# nm_mcu.net
KiCad netlist of a schematic drawn in Altium Designer
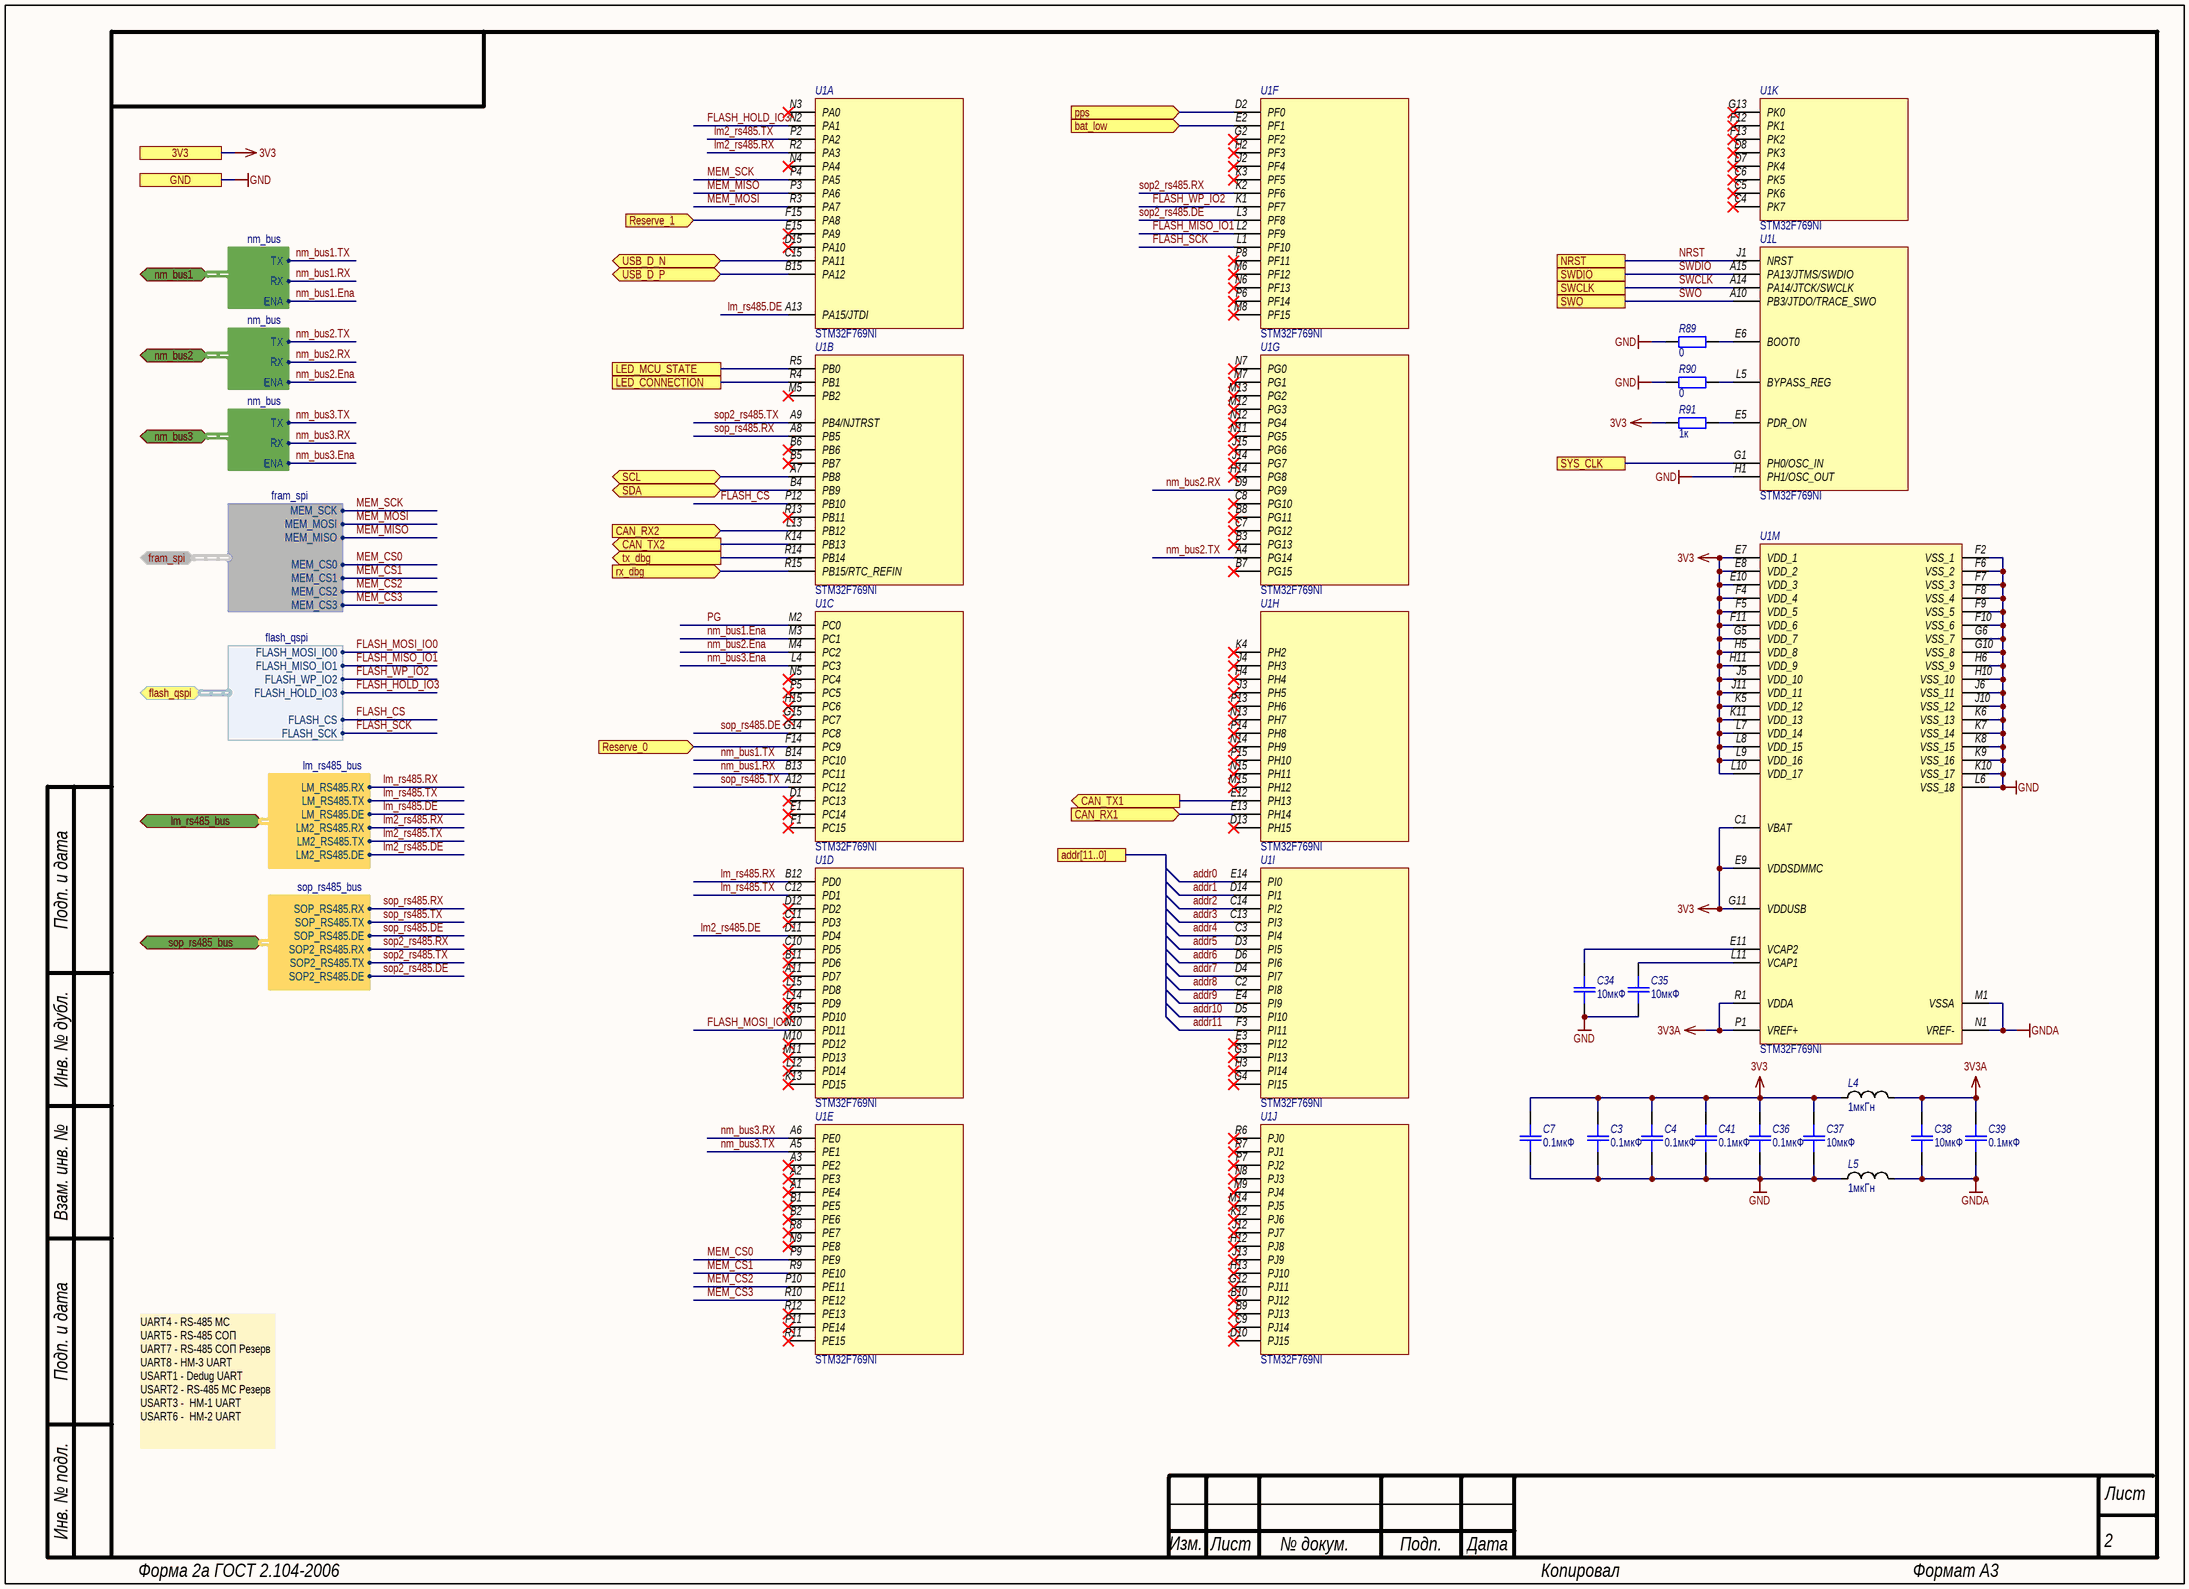
[diagram p0: nm_mcu.SchDoc]

(export (version "E")
  (design (tool "Eeschema 10.0.6"))
  (components
    (comp (ref "C3")
      (value "0.1мкФ")
      (footprint "SMD_C0603")
      (description "Capacitor")
      (libsource (lib "Passive") (part "Capacitor"))
    )
    (comp (ref "C4")
      (value "0.1мкФ")
      (footprint "SMD_C0603")
      (description "Capacitor")
      (libsource (lib "Passive") (part "Capacitor"))
    )
    (comp (ref "C7")
      (value "0.1мкФ")
      (footprint "SMD_C0603")
      (description "Capacitor")
      (libsource (lib "Passive") (part "Capacitor"))
    )
    (comp (ref "C34")
      (value "10мкФ")
      (footprint "SMD_C0603")
      (description "Capacitor")
      (libsource (lib "Passive") (part "Capacitor"))
    )
    (comp (ref "C35")
      (value "10мкФ")
      (footprint "SMD_C0603")
      (description "Capacitor")
      (libsource (lib "Passive") (part "Capacitor"))
    )
    (comp (ref "C36")
      (value "0.1мкФ")
      (footprint "SMD_C0603")
      (description "Capacitor")
      (libsource (lib "Passive") (part "Capacitor"))
    )
    (comp (ref "C37")
      (value "10мкФ")
      (footprint "SMD_C0603")
      (description "Capacitor")
      (libsource (lib "Passive") (part "Capacitor"))
    )
    (comp (ref "C38")
      (value "10мкФ")
      (footprint "SMD_C0603")
      (description "Capacitor")
      (libsource (lib "Passive") (part "Capacitor"))
    )
    (comp (ref "C39")
      (value "0.1мкФ")
      (footprint "SMD_C0603")
      (description "Capacitor")
      (libsource (lib "Passive") (part "Capacitor"))
    )
    (comp (ref "C41")
      (value "0.1мкФ")
      (footprint "SMD_C0603")
      (description "Capacitor")
      (libsource (lib "Passive") (part "Capacitor"))
    )
    (comp (ref "L4")
      (value "1мкГн")
      (footprint "SMD_0805")
      (description "Inductor")
      (libsource (lib "Passive") (part "Inductor"))
    )
    (comp (ref "L5")
      (value "1мкГн")
      (footprint "SMD_0805")
      (description "Inductor")
      (libsource (lib "Passive") (part "Inductor"))
    )
    (comp (ref "R89")
      (value "0")
      (footprint "SMD_0603")
      (description "Resistor")
      (libsource (lib "Passive") (part "Resistor"))
    )
    (comp (ref "R90")
      (value "0")
      (footprint "SMD_0603")
      (description "Resistor")
      (libsource (lib "Passive") (part "Resistor"))
    )
    (comp (ref "R91")
      (value "1к")
      (footprint "SMD_0603")
      (description "Resistor")
      (libsource (lib "Passive") (part "Resistor"))
    )
    (comp (ref "U1")
      (value "STM32F769NI")
      (footprint "BGA216C80P15X15_1300X1300X110")
      (fields (field (name "НАИМЕНОВАНИЕ") "STM32F769NI"))
      (libsource (lib "STM32F769NI") (part "STM32F769NI"))
    )
  )
  (nets
    (net (code "6") (name "/CAN_RX1") (class "Default")
      (node (ref "U1") (pin "E13") (pinfunction "PH14_E13") (pintype "passive"))
    )
    (net (code "7") (name "/CAN_RX2") (class "Default")
      (node (ref "U1") (pin "L13") (pinfunction "PB12_L13") (pintype "passive"))
    )
    (net (code "8") (name "/CAN_TX1") (class "Default")
      (node (ref "U1") (pin "E12") (pinfunction "PH13_E12") (pintype "passive"))
    )
    (net (code "9") (name "/CAN_TX2") (class "Default")
      (node (ref "U1") (pin "K14") (pinfunction "PB13_K14") (pintype "passive"))
    )
    (net (code "10") (name "/FLASH_CS") (class "Default")
      (node (ref "U1") (pin "P12") (pinfunction "PB10_P12") (pintype "passive"))
    )
    (net (code "11") (name "/FLASH_HOLD_IO3") (class "Default")
      (node (ref "U1") (pin "N2") (pinfunction "PA1_N2") (pintype "passive"))
    )
    (net (code "12") (name "/FLASH_MISO_IO1") (class "Default")
      (node (ref "U1") (pin "L2") (pinfunction "PF9_L2") (pintype "passive"))
    )
    (net (code "13") (name "/FLASH_MOSI_IO0") (class "Default")
      (node (ref "U1") (pin "N10") (pinfunction "PD11_N10") (pintype "passive"))
    )
    (net (code "14") (name "/FLASH_SCK") (class "Default")
      (node (ref "U1") (pin "L1") (pinfunction "PF10_L1") (pintype "passive"))
    )
    (net (code "15") (name "/FLASH_WP_IO2") (class "Default")
      (node (ref "U1") (pin "K1") (pinfunction "PF7_K1") (pintype "passive"))
    )
    (net (code "16") (name "/LED_CONNECTION") (class "Default")
      (node (ref "U1") (pin "R4") (pinfunction "PB1_R4") (pintype "passive"))
    )
    (net (code "17") (name "/LED_MCU_STATE") (class "Default")
      (node (ref "U1") (pin "R5") (pinfunction "PB0_R5") (pintype "passive"))
    )
    (net (code "18") (name "/MEM_CS0") (class "Default")
      (node (ref "U1") (pin "P9") (pinfunction "PE9_P9") (pintype "passive"))
    )
    (net (code "19") (name "/MEM_CS1") (class "Default")
      (node (ref "U1") (pin "R9") (pinfunction "PE10_R9") (pintype "passive"))
    )
    (net (code "20") (name "/MEM_CS2") (class "Default")
      (node (ref "U1") (pin "P10") (pinfunction "PE11_P10") (pintype "passive"))
    )
    (net (code "21") (name "/MEM_CS3") (class "Default")
      (node (ref "U1") (pin "R10") (pinfunction "PE12_R10") (pintype "passive"))
    )
    (net (code "22") (name "/MEM_MISO") (class "Default")
      (node (ref "U1") (pin "P3") (pinfunction "PA6_P3") (pintype "passive"))
    )
    (net (code "23") (name "/MEM_MOSI") (class "Default")
      (node (ref "U1") (pin "R3") (pinfunction "PA7_R3") (pintype "passive"))
    )
    (net (code "24") (name "/MEM_SCK") (class "Default")
      (node (ref "U1") (pin "P4") (pinfunction "PA5_P4") (pintype "passive"))
    )
    (net (code "25") (name "/NRST") (class "Default")
      (node (ref "U1") (pin "J1") (pinfunction "NRST_J1") (pintype "passive"))
    )
    (net (code "26") (name "/PG") (class "Default")
      (node (ref "U1") (pin "M2") (pinfunction "PC0_M2") (pintype "passive"))
    )
    (net (code "27") (name "/Reserve_0") (class "Default")
      (node (ref "U1") (pin "F14") (pinfunction "PC9_F14") (pintype "passive"))
    )
    (net (code "28") (name "/Reserve_1") (class "Default")
      (node (ref "U1") (pin "F15") (pinfunction "PA8_F15") (pintype "passive"))
    )
    (net (code "29") (name "/SCL") (class "Default")
      (node (ref "U1") (pin "A7") (pinfunction "PB8_A7") (pintype "passive"))
    )
    (net (code "30") (name "/SDA") (class "Default")
      (node (ref "U1") (pin "B4") (pinfunction "PB9_B4") (pintype "passive"))
    )
    (net (code "31") (name "/SWCLK") (class "Default")
      (node (ref "U1") (pin "A14") (pinfunction "PA14/JTCK/SWCLK_A14") (pintype "passive"))
    )
    (net (code "32") (name "/SWDIO") (class "Default")
      (node (ref "U1") (pin "A15") (pinfunction "PA13/JTMS/SWDIO_A15") (pintype "passive"))
    )
    (net (code "33") (name "/SWO") (class "Default")
      (node (ref "U1") (pin "A10") (pinfunction "PB3/JTDO/TRACE_SWO_A10") (pintype "passive"))
    )
    (net (code "34") (name "/SYS_CLK") (class "Default")
      (node (ref "U1") (pin "G1") (pinfunction "PH0/OSC_IN_G1") (pintype "passive"))
    )
    (net (code "35") (name "/USB_D_N") (class "Default")
      (node (ref "U1") (pin "C15") (pinfunction "PA11_C15") (pintype "passive"))
    )
    (net (code "36") (name "/USB_D_P") (class "Default")
      (node (ref "U1") (pin "B15") (pinfunction "PA12_B15") (pintype "passive"))
    )
    (net (code "37") (name "/addr0") (class "Default")
      (node (ref "U1") (pin "E14") (pinfunction "PI0_E14") (pintype "passive"))
    )
    (net (code "38") (name "/addr1") (class "Default")
      (node (ref "U1") (pin "D14") (pinfunction "PI1_D14") (pintype "passive"))
    )
    (net (code "39") (name "/addr2") (class "Default")
      (node (ref "U1") (pin "C14") (pinfunction "PI2_C14") (pintype "passive"))
    )
    (net (code "40") (name "/addr3") (class "Default")
      (node (ref "U1") (pin "C13") (pinfunction "PI3_C13") (pintype "passive"))
    )
    (net (code "41") (name "/addr4") (class "Default")
      (node (ref "U1") (pin "C3") (pinfunction "PI4_C3") (pintype "passive"))
    )
    (net (code "42") (name "/addr5") (class "Default")
      (node (ref "U1") (pin "D3") (pinfunction "PI5_D3") (pintype "passive"))
    )
    (net (code "43") (name "/addr6") (class "Default")
      (node (ref "U1") (pin "D6") (pinfunction "PI6_D6") (pintype "passive"))
    )
    (net (code "44") (name "/addr7") (class "Default")
      (node (ref "U1") (pin "D4") (pinfunction "PI7_D4") (pintype "passive"))
    )
    (net (code "45") (name "/addr8") (class "Default")
      (node (ref "U1") (pin "C2") (pinfunction "PI8_C2") (pintype "passive"))
    )
    (net (code "46") (name "/addr9") (class "Default")
      (node (ref "U1") (pin "E4") (pinfunction "PI9_E4") (pintype "passive"))
    )
    (net (code "47") (name "/addr10") (class "Default")
      (node (ref "U1") (pin "D5") (pinfunction "PI10_D5") (pintype "passive"))
    )
    (net (code "48") (name "/addr11") (class "Default")
      (node (ref "U1") (pin "F3") (pinfunction "PI11_F3") (pintype "passive"))
    )
    (net (code "50") (name "/bat_low") (class "Default")
      (node (ref "U1") (pin "E2") (pinfunction "PF1_E2") (pintype "passive"))
    )
    (net (code "51") (name "/lm2_rs485.DE") (class "Default")
      (node (ref "U1") (pin "D11") (pinfunction "PD4_D11") (pintype "passive"))
    )
    (net (code "52") (name "/lm2_rs485.RX") (class "Default")
      (node (ref "U1") (pin "R2") (pinfunction "PA3_R2") (pintype "passive"))
    )
    (net (code "53") (name "/lm2_rs485.TX") (class "Default")
      (node (ref "U1") (pin "P2") (pinfunction "PA2_P2") (pintype "passive"))
    )
    (net (code "54") (name "/lm_rs485.DE") (class "Default")
      (node (ref "U1") (pin "A13") (pinfunction "PA15/JTDI_A13") (pintype "passive"))
    )
    (net (code "55") (name "/lm_rs485.RX") (class "Default")
      (node (ref "U1") (pin "B12") (pinfunction "PD0_B12") (pintype "passive"))
    )
    (net (code "56") (name "/lm_rs485.TX") (class "Default")
      (node (ref "U1") (pin "C12") (pinfunction "PD1_C12") (pintype "passive"))
    )
    (net (code "57") (name "/nm_bus1.Ena") (class "Default")
      (node (ref "U1") (pin "M3") (pinfunction "PC1_M3") (pintype "passive"))
    )
    (net (code "58") (name "/nm_bus1.RX") (class "Default")
      (node (ref "U1") (pin "B13") (pinfunction "PC11_B13") (pintype "passive"))
    )
    (net (code "59") (name "/nm_bus1.TX") (class "Default")
      (node (ref "U1") (pin "B14") (pinfunction "PC10_B14") (pintype "passive"))
    )
    (net (code "60") (name "/nm_bus2.Ena") (class "Default")
      (node (ref "U1") (pin "M4") (pinfunction "PC2_M4") (pintype "passive"))
    )
    (net (code "61") (name "/nm_bus2.RX") (class "Default")
      (node (ref "U1") (pin "D9") (pinfunction "PG9_D9") (pintype "passive"))
    )
    (net (code "62") (name "/nm_bus2.TX") (class "Default")
      (node (ref "U1") (pin "A4") (pinfunction "PG14_A4") (pintype "passive"))
    )
    (net (code "63") (name "/nm_bus3.Ena") (class "Default")
      (node (ref "U1") (pin "L4") (pinfunction "PC3_L4") (pintype "passive"))
    )
    (net (code "64") (name "/nm_bus3.RX") (class "Default")
      (node (ref "U1") (pin "A6") (pinfunction "PE0_A6") (pintype "passive"))
    )
    (net (code "65") (name "/nm_bus3.TX") (class "Default")
      (node (ref "U1") (pin "A5") (pinfunction "PE1_A5") (pintype "passive"))
    )
    (net (code "66") (name "/pps") (class "Default")
      (node (ref "U1") (pin "D2") (pinfunction "PF0_D2") (pintype "passive"))
    )
    (net (code "67") (name "/rx_dbg") (class "Default")
      (node (ref "U1") (pin "R15") (pinfunction "PB15/RTC_REFIN_R15") (pintype "passive"))
    )
    (net (code "68") (name "/sop2_rs485.DE") (class "Default")
      (node (ref "U1") (pin "L3") (pinfunction "PF8_L3") (pintype "passive"))
    )
    (net (code "69") (name "/sop2_rs485.RX") (class "Default")
      (node (ref "U1") (pin "K2") (pinfunction "PF6_K2") (pintype "passive"))
    )
    (net (code "70") (name "/sop2_rs485.TX") (class "Default")
      (node (ref "U1") (pin "A9") (pinfunction "PB4/NJTRST_A9") (pintype "passive"))
    )
    (net (code "71") (name "/sop_rs485.DE") (class "Default")
      (node (ref "U1") (pin "G14") (pinfunction "PC8_G14") (pintype "passive"))
    )
    (net (code "72") (name "/sop_rs485.RX") (class "Default")
      (node (ref "U1") (pin "A8") (pinfunction "PB5_A8") (pintype "passive"))
    )
    (net (code "73") (name "/sop_rs485.TX") (class "Default")
      (node (ref "U1") (pin "A12") (pinfunction "PC12_A12") (pintype "passive"))
    )
    (net (code "74") (name "/tx_dbg") (class "Default")
      (node (ref "U1") (pin "R14") (pinfunction "PB14_R14") (pintype "passive"))
    )
    (net (code "80") (name "3V3") (class "Default")
      (node (ref "C3") (pin "2") (pinfunction "2_2") (pintype "passive"))
      (node (ref "C36") (pin "2") (pinfunction "2_2") (pintype "passive"))
      (node (ref "C37") (pin "2") (pinfunction "2_2") (pintype "passive"))
      (node (ref "C4") (pin "2") (pinfunction "2_2") (pintype "passive"))
      (node (ref "C41") (pin "2") (pinfunction "2_2") (pintype "passive"))
      (node (ref "C7") (pin "2") (pinfunction "2_2") (pintype "passive"))
      (node (ref "L4") (pin "1") (pinfunction "1_1") (pintype "passive"))
      (node (ref "R91") (pin "1") (pinfunction "1_1") (pintype "passive"))
      (node (ref "U1") (pin "C1") (pinfunction "VBAT_C1") (pintype "passive"))
      (node (ref "U1") (pin "E10") (pinfunction "VDD_3_E10") (pintype "passive"))
      (node (ref "U1") (pin "E7") (pinfunction "VDD_1_E7") (pintype "passive"))
      (node (ref "U1") (pin "E8") (pinfunction "VDD_2_E8") (pintype "passive"))
      (node (ref "U1") (pin "E9") (pinfunction "VDDSDMMC_E9") (pintype "passive"))
      (node (ref "U1") (pin "F11") (pinfunction "VDD_6_F11") (pintype "passive"))
      (node (ref "U1") (pin "F4") (pinfunction "VDD_4_F4") (pintype "passive"))
      (node (ref "U1") (pin "F5") (pinfunction "VDD_5_F5") (pintype "passive"))
      (node (ref "U1") (pin "G11") (pinfunction "VDDUSB_G11") (pintype "passive"))
      (node (ref "U1") (pin "G5") (pinfunction "VDD_7_G5") (pintype "passive"))
      (node (ref "U1") (pin "H11") (pinfunction "VDD_9_H11") (pintype "passive"))
      (node (ref "U1") (pin "H5") (pinfunction "VDD_8_H5") (pintype "passive"))
      (node (ref "U1") (pin "J11") (pinfunction "VDD_11_J11") (pintype "passive"))
      (node (ref "U1") (pin "J5") (pinfunction "VDD_10_J5") (pintype "passive"))
      (node (ref "U1") (pin "K11") (pinfunction "VDD_13_K11") (pintype "passive"))
      (node (ref "U1") (pin "K5") (pinfunction "VDD_12_K5") (pintype "passive"))
      (node (ref "U1") (pin "L10") (pinfunction "VDD_17_L10") (pintype "passive"))
      (node (ref "U1") (pin "L7") (pinfunction "VDD_14_L7") (pintype "passive"))
      (node (ref "U1") (pin "L8") (pinfunction "VDD_15_L8") (pintype "passive"))
      (node (ref "U1") (pin "L9") (pinfunction "VDD_16_L9") (pintype "passive"))
    )
    (net (code "81") (name "3V3A") (class "Default")
      (node (ref "C38") (pin "2") (pinfunction "2_2") (pintype "passive"))
      (node (ref "C39") (pin "2") (pinfunction "2_2") (pintype "passive"))
      (node (ref "L4") (pin "2") (pinfunction "2_2") (pintype "passive"))
      (node (ref "U1") (pin "P1") (pinfunction "VREF+_P1") (pintype "passive"))
      (node (ref "U1") (pin "R1") (pinfunction "VDDA_R1") (pintype "passive"))
    )
    (net (code "82") (name "GND") (class "Default")
      (node (ref "C3") (pin "1") (pinfunction "1_1") (pintype "passive"))
      (node (ref "C34") (pin "1") (pinfunction "1_1") (pintype "passive"))
      (node (ref "C35") (pin "1") (pinfunction "1_1") (pintype "passive"))
      (node (ref "C36") (pin "1") (pinfunction "1_1") (pintype "passive"))
      (node (ref "C37") (pin "1") (pinfunction "1_1") (pintype "passive"))
      (node (ref "C4") (pin "1") (pinfunction "1_1") (pintype "passive"))
      (node (ref "C41") (pin "1") (pinfunction "1_1") (pintype "passive"))
      (node (ref "C7") (pin "1") (pinfunction "1_1") (pintype "passive"))
      (node (ref "L5") (pin "1") (pinfunction "1_1") (pintype "passive"))
      (node (ref "R89") (pin "1") (pinfunction "1_1") (pintype "passive"))
      (node (ref "R90") (pin "1") (pinfunction "1_1") (pintype "passive"))
      (node (ref "U1") (pin "F10") (pinfunction "VSS_6_F10") (pintype "passive"))
      (node (ref "U1") (pin "F2") (pinfunction "VSS_1_F2") (pintype "passive"))
      (node (ref "U1") (pin "F6") (pinfunction "VSS_2_F6") (pintype "passive"))
      (node (ref "U1") (pin "F7") (pinfunction "VSS_3_F7") (pintype "passive"))
      (node (ref "U1") (pin "F8") (pinfunction "VSS_4_F8") (pintype "passive"))
      (node (ref "U1") (pin "F9") (pinfunction "VSS_5_F9") (pintype "passive"))
      (node (ref "U1") (pin "G10") (pinfunction "VSS_8_G10") (pintype "passive"))
      (node (ref "U1") (pin "G6") (pinfunction "VSS_7_G6") (pintype "passive"))
      (node (ref "U1") (pin "H1") (pinfunction "PH1/OSC_OUT_H1") (pintype "passive"))
      (node (ref "U1") (pin "H10") (pinfunction "VSS_10_H10") (pintype "passive"))
      (node (ref "U1") (pin "H6") (pinfunction "VSS_9_H6") (pintype "passive"))
      (node (ref "U1") (pin "J10") (pinfunction "VSS_12_J10") (pintype "passive"))
      (node (ref "U1") (pin "J6") (pinfunction "VSS_11_J6") (pintype "passive"))
      (node (ref "U1") (pin "K10") (pinfunction "VSS_17_K10") (pintype "passive"))
      (node (ref "U1") (pin "K6") (pinfunction "VSS_13_K6") (pintype "passive"))
      (node (ref "U1") (pin "K7") (pinfunction "VSS_14_K7") (pintype "passive"))
      (node (ref "U1") (pin "K8") (pinfunction "VSS_15_K8") (pintype "passive"))
      (node (ref "U1") (pin "K9") (pinfunction "VSS_16_K9") (pintype "passive"))
      (node (ref "U1") (pin "L6") (pinfunction "VSS_18_L6") (pintype "passive"))
    )
    (net (code "83") (name "GNDA") (class "Default")
      (node (ref "C38") (pin "1") (pinfunction "1_1") (pintype "passive"))
      (node (ref "C39") (pin "1") (pinfunction "1_1") (pintype "passive"))
      (node (ref "L5") (pin "2") (pinfunction "2_2") (pintype "passive"))
      (node (ref "U1") (pin "M1") (pinfunction "VSSA_M1") (pintype "passive"))
      (node (ref "U1") (pin "N1") (pinfunction "VREF-_N1") (pintype "passive"))
    )
    (net (code "84") (name "Net-(U1L-BOOT0)") (class "Default")
      (node (ref "R89") (pin "2") (pinfunction "2_2") (pintype "passive"))
      (node (ref "U1") (pin "E6") (pinfunction "BOOT0_E6") (pintype "passive"))
    )
    (net (code "85") (name "Net-(U1L-BYPASS_REG)") (class "Default")
      (node (ref "R90") (pin "2") (pinfunction "2_2") (pintype "passive"))
      (node (ref "U1") (pin "L5") (pinfunction "BYPASS_REG_L5") (pintype "passive"))
    )
    (net (code "86") (name "Net-(U1L-PDR_ON)") (class "Default")
      (node (ref "R91") (pin "2") (pinfunction "2_2") (pintype "passive"))
      (node (ref "U1") (pin "E5") (pinfunction "PDR_ON_E5") (pintype "passive"))
    )
    (net (code "87") (name "Net-(U1M-VCAP1)") (class "Default")
      (node (ref "C35") (pin "2") (pinfunction "2_2") (pintype "passive"))
      (node (ref "U1") (pin "L11") (pinfunction "VCAP1_L11") (pintype "passive"))
    )
    (net (code "88") (name "Net-(U1M-VCAP2)") (class "Default")
      (node (ref "C34") (pin "2") (pinfunction "2_2") (pintype "passive"))
      (node (ref "U1") (pin "E11") (pinfunction "VCAP2_E11") (pintype "passive"))
    )
    (net (code "89") (name "unconnected-(U1A-PA0-PadN3)") (class "Default")
      (node (ref "U1") (pin "N3") (pinfunction "PA0_N3") (pintype "passive+no_connect"))
    )
    (net (code "90") (name "unconnected-(U1A-PA4-PadN4)") (class "Default")
      (node (ref "U1") (pin "N4") (pinfunction "PA4_N4") (pintype "passive+no_connect"))
    )
    (net (code "91") (name "unconnected-(U1A-PA9-PadE15)") (class "Default")
      (node (ref "U1") (pin "E15") (pinfunction "PA9_E15") (pintype "passive+no_connect"))
    )
    (net (code "92") (name "unconnected-(U1A-PA10-PadD15)") (class "Default")
      (node (ref "U1") (pin "D15") (pinfunction "PA10_D15") (pintype "passive+no_connect"))
    )
    (net (code "93") (name "unconnected-(U1B-PB2-PadM5)") (class "Default")
      (node (ref "U1") (pin "M5") (pinfunction "PB2_M5") (pintype "passive+no_connect"))
    )
    (net (code "94") (name "unconnected-(U1B-PB6-PadB6)") (class "Default")
      (node (ref "U1") (pin "B6") (pinfunction "PB6_B6") (pintype "passive+no_connect"))
    )
    (net (code "95") (name "unconnected-(U1B-PB7-PadB5)") (class "Default")
      (node (ref "U1") (pin "B5") (pinfunction "PB7_B5") (pintype "passive+no_connect"))
    )
    (net (code "96") (name "unconnected-(U1B-PB11-PadR13)") (class "Default")
      (node (ref "U1") (pin "R13") (pinfunction "PB11_R13") (pintype "passive+no_connect"))
    )
    (net (code "97") (name "unconnected-(U1C-PC4-PadN5)") (class "Default")
      (node (ref "U1") (pin "N5") (pinfunction "PC4_N5") (pintype "passive+no_connect"))
    )
    (net (code "98") (name "unconnected-(U1C-PC5-PadP5)") (class "Default")
      (node (ref "U1") (pin "P5") (pinfunction "PC5_P5") (pintype "passive+no_connect"))
    )
    (net (code "99") (name "unconnected-(U1C-PC6-PadH15)") (class "Default")
      (node (ref "U1") (pin "H15") (pinfunction "PC6_H15") (pintype "passive+no_connect"))
    )
    (net (code "100") (name "unconnected-(U1C-PC7-PadG15)") (class "Default")
      (node (ref "U1") (pin "G15") (pinfunction "PC7_G15") (pintype "passive+no_connect"))
    )
    (net (code "101") (name "unconnected-(U1C-PC13-PadD1)") (class "Default")
      (node (ref "U1") (pin "D1") (pinfunction "PC13_D1") (pintype "passive+no_connect"))
    )
    (net (code "102") (name "unconnected-(U1C-PC14-PadE1)") (class "Default")
      (node (ref "U1") (pin "E1") (pinfunction "PC14_E1") (pintype "passive+no_connect"))
    )
    (net (code "103") (name "unconnected-(U1C-PC15-PadF1)") (class "Default")
      (node (ref "U1") (pin "F1") (pinfunction "PC15_F1") (pintype "passive+no_connect"))
    )
    (net (code "104") (name "unconnected-(U1D-PD2-PadD12)") (class "Default")
      (node (ref "U1") (pin "D12") (pinfunction "PD2_D12") (pintype "passive+no_connect"))
    )
    (net (code "105") (name "unconnected-(U1D-PD3-PadC11)") (class "Default")
      (node (ref "U1") (pin "C11") (pinfunction "PD3_C11") (pintype "passive+no_connect"))
    )
    (net (code "106") (name "unconnected-(U1D-PD5-PadC10)") (class "Default")
      (node (ref "U1") (pin "C10") (pinfunction "PD5_C10") (pintype "passive+no_connect"))
    )
    (net (code "107") (name "unconnected-(U1D-PD6-PadB11)") (class "Default")
      (node (ref "U1") (pin "B11") (pinfunction "PD6_B11") (pintype "passive+no_connect"))
    )
    (net (code "108") (name "unconnected-(U1D-PD7-PadA11)") (class "Default")
      (node (ref "U1") (pin "A11") (pinfunction "PD7_A11") (pintype "passive+no_connect"))
    )
    (net (code "109") (name "unconnected-(U1D-PD8-PadL15)") (class "Default")
      (node (ref "U1") (pin "L15") (pinfunction "PD8_L15") (pintype "passive+no_connect"))
    )
    (net (code "110") (name "unconnected-(U1D-PD9-PadL14)") (class "Default")
      (node (ref "U1") (pin "L14") (pinfunction "PD9_L14") (pintype "passive+no_connect"))
    )
    (net (code "111") (name "unconnected-(U1D-PD10-PadK15)") (class "Default")
      (node (ref "U1") (pin "K15") (pinfunction "PD10_K15") (pintype "passive+no_connect"))
    )
    (net (code "112") (name "unconnected-(U1D-PD12-PadM10)") (class "Default")
      (node (ref "U1") (pin "M10") (pinfunction "PD12_M10") (pintype "passive+no_connect"))
    )
    (net (code "113") (name "unconnected-(U1D-PD13-PadM11)") (class "Default")
      (node (ref "U1") (pin "M11") (pinfunction "PD13_M11") (pintype "passive+no_connect"))
    )
    (net (code "114") (name "unconnected-(U1D-PD14-PadL12)") (class "Default")
      (node (ref "U1") (pin "L12") (pinfunction "PD14_L12") (pintype "passive+no_connect"))
    )
    (net (code "115") (name "unconnected-(U1D-PD15-PadK13)") (class "Default")
      (node (ref "U1") (pin "K13") (pinfunction "PD15_K13") (pintype "passive+no_connect"))
    )
    (net (code "116") (name "unconnected-(U1E-PE2-PadA3)") (class "Default")
      (node (ref "U1") (pin "A3") (pinfunction "PE2_A3") (pintype "passive+no_connect"))
    )
    (net (code "117") (name "unconnected-(U1E-PE3-PadA2)") (class "Default")
      (node (ref "U1") (pin "A2") (pinfunction "PE3_A2") (pintype "passive+no_connect"))
    )
    (net (code "118") (name "unconnected-(U1E-PE4-PadA1)") (class "Default")
      (node (ref "U1") (pin "A1") (pinfunction "PE4_A1") (pintype "passive+no_connect"))
    )
    (net (code "119") (name "unconnected-(U1E-PE5-PadB1)") (class "Default")
      (node (ref "U1") (pin "B1") (pinfunction "PE5_B1") (pintype "passive+no_connect"))
    )
    (net (code "120") (name "unconnected-(U1E-PE6-PadB2)") (class "Default")
      (node (ref "U1") (pin "B2") (pinfunction "PE6_B2") (pintype "passive+no_connect"))
    )
    (net (code "121") (name "unconnected-(U1E-PE7-PadR8)") (class "Default")
      (node (ref "U1") (pin "R8") (pinfunction "PE7_R8") (pintype "passive+no_connect"))
    )
    (net (code "122") (name "unconnected-(U1E-PE8-PadN9)") (class "Default")
      (node (ref "U1") (pin "N9") (pinfunction "PE8_N9") (pintype "passive+no_connect"))
    )
    (net (code "123") (name "unconnected-(U1E-PE13-PadR12)") (class "Default")
      (node (ref "U1") (pin "R12") (pinfunction "PE13_R12") (pintype "passive+no_connect"))
    )
    (net (code "124") (name "unconnected-(U1E-PE14-PadP11)") (class "Default")
      (node (ref "U1") (pin "P11") (pinfunction "PE14_P11") (pintype "passive+no_connect"))
    )
    (net (code "125") (name "unconnected-(U1E-PE15-PadR11)") (class "Default")
      (node (ref "U1") (pin "R11") (pinfunction "PE15_R11") (pintype "passive+no_connect"))
    )
    (net (code "126") (name "unconnected-(U1F-PF2-PadG2)") (class "Default")
      (node (ref "U1") (pin "G2") (pinfunction "PF2_G2") (pintype "passive+no_connect"))
    )
    (net (code "127") (name "unconnected-(U1F-PF3-PadH2)") (class "Default")
      (node (ref "U1") (pin "H2") (pinfunction "PF3_H2") (pintype "passive+no_connect"))
    )
    (net (code "128") (name "unconnected-(U1F-PF4-PadJ2)") (class "Default")
      (node (ref "U1") (pin "J2") (pinfunction "PF4_J2") (pintype "passive+no_connect"))
    )
    (net (code "129") (name "unconnected-(U1F-PF5-PadK3)") (class "Default")
      (node (ref "U1") (pin "K3") (pinfunction "PF5_K3") (pintype "passive+no_connect"))
    )
    (net (code "130") (name "unconnected-(U1F-PF11-PadP8)") (class "Default")
      (node (ref "U1") (pin "P8") (pinfunction "PF11_P8") (pintype "passive+no_connect"))
    )
    (net (code "131") (name "unconnected-(U1F-PF12-PadM6)") (class "Default")
      (node (ref "U1") (pin "M6") (pinfunction "PF12_M6") (pintype "passive+no_connect"))
    )
    (net (code "132") (name "unconnected-(U1F-PF13-PadN6)") (class "Default")
      (node (ref "U1") (pin "N6") (pinfunction "PF13_N6") (pintype "passive+no_connect"))
    )
    (net (code "133") (name "unconnected-(U1F-PF14-PadP6)") (class "Default")
      (node (ref "U1") (pin "P6") (pinfunction "PF14_P6") (pintype "passive+no_connect"))
    )
    (net (code "134") (name "unconnected-(U1F-PF15-PadM8)") (class "Default")
      (node (ref "U1") (pin "M8") (pinfunction "PF15_M8") (pintype "passive+no_connect"))
    )
    (net (code "135") (name "unconnected-(U1G-PG0-PadN7)") (class "Default")
      (node (ref "U1") (pin "N7") (pinfunction "PG0_N7") (pintype "passive+no_connect"))
    )
    (net (code "136") (name "unconnected-(U1G-PG1-PadM7)") (class "Default")
      (node (ref "U1") (pin "M7") (pinfunction "PG1_M7") (pintype "passive+no_connect"))
    )
    (net (code "137") (name "unconnected-(U1G-PG2-PadM13)") (class "Default")
      (node (ref "U1") (pin "M13") (pinfunction "PG2_M13") (pintype "passive+no_connect"))
    )
    (net (code "138") (name "unconnected-(U1G-PG3-PadM12)") (class "Default")
      (node (ref "U1") (pin "M12") (pinfunction "PG3_M12") (pintype "passive+no_connect"))
    )
    (net (code "139") (name "unconnected-(U1G-PG4-PadN12)") (class "Default")
      (node (ref "U1") (pin "N12") (pinfunction "PG4_N12") (pintype "passive+no_connect"))
    )
    (net (code "140") (name "unconnected-(U1G-PG5-PadN11)") (class "Default")
      (node (ref "U1") (pin "N11") (pinfunction "PG5_N11") (pintype "passive+no_connect"))
    )
    (net (code "141") (name "unconnected-(U1G-PG6-PadJ15)") (class "Default")
      (node (ref "U1") (pin "J15") (pinfunction "PG6_J15") (pintype "passive+no_connect"))
    )
    (net (code "142") (name "unconnected-(U1G-PG7-PadJ14)") (class "Default")
      (node (ref "U1") (pin "J14") (pinfunction "PG7_J14") (pintype "passive+no_connect"))
    )
    (net (code "143") (name "unconnected-(U1G-PG8-PadH14)") (class "Default")
      (node (ref "U1") (pin "H14") (pinfunction "PG8_H14") (pintype "passive+no_connect"))
    )
    (net (code "144") (name "unconnected-(U1G-PG10-PadC8)") (class "Default")
      (node (ref "U1") (pin "C8") (pinfunction "PG10_C8") (pintype "passive+no_connect"))
    )
    (net (code "145") (name "unconnected-(U1G-PG11-PadB8)") (class "Default")
      (node (ref "U1") (pin "B8") (pinfunction "PG11_B8") (pintype "passive+no_connect"))
    )
    (net (code "146") (name "unconnected-(U1G-PG12-PadC7)") (class "Default")
      (node (ref "U1") (pin "C7") (pinfunction "PG12_C7") (pintype "passive+no_connect"))
    )
    (net (code "147") (name "unconnected-(U1G-PG13-PadB3)") (class "Default")
      (node (ref "U1") (pin "B3") (pinfunction "PG13_B3") (pintype "passive+no_connect"))
    )
    (net (code "148") (name "unconnected-(U1G-PG15-PadB7)") (class "Default")
      (node (ref "U1") (pin "B7") (pinfunction "PG15_B7") (pintype "passive+no_connect"))
    )
    (net (code "149") (name "unconnected-(U1H-PH2-PadK4)") (class "Default")
      (node (ref "U1") (pin "K4") (pinfunction "PH2_K4") (pintype "passive+no_connect"))
    )
    (net (code "150") (name "unconnected-(U1H-PH3-PadJ4)") (class "Default")
      (node (ref "U1") (pin "J4") (pinfunction "PH3_J4") (pintype "passive+no_connect"))
    )
    (net (code "151") (name "unconnected-(U1H-PH4-PadH4)") (class "Default")
      (node (ref "U1") (pin "H4") (pinfunction "PH4_H4") (pintype "passive+no_connect"))
    )
    (net (code "152") (name "unconnected-(U1H-PH5-PadJ3)") (class "Default")
      (node (ref "U1") (pin "J3") (pinfunction "PH5_J3") (pintype "passive+no_connect"))
    )
    (net (code "153") (name "unconnected-(U1H-PH6-PadP13)") (class "Default")
      (node (ref "U1") (pin "P13") (pinfunction "PH6_P13") (pintype "passive+no_connect"))
    )
    (net (code "154") (name "unconnected-(U1H-PH7-PadN13)") (class "Default")
      (node (ref "U1") (pin "N13") (pinfunction "PH7_N13") (pintype "passive+no_connect"))
    )
    (net (code "155") (name "unconnected-(U1H-PH8-PadP14)") (class "Default")
      (node (ref "U1") (pin "P14") (pinfunction "PH8_P14") (pintype "passive+no_connect"))
    )
    (net (code "156") (name "unconnected-(U1H-PH9-PadN14)") (class "Default")
      (node (ref "U1") (pin "N14") (pinfunction "PH9_N14") (pintype "passive+no_connect"))
    )
    (net (code "157") (name "unconnected-(U1H-PH10-PadP15)") (class "Default")
      (node (ref "U1") (pin "P15") (pinfunction "PH10_P15") (pintype "passive+no_connect"))
    )
    (net (code "158") (name "unconnected-(U1H-PH11-PadN15)") (class "Default")
      (node (ref "U1") (pin "N15") (pinfunction "PH11_N15") (pintype "passive+no_connect"))
    )
    (net (code "159") (name "unconnected-(U1H-PH12-PadM15)") (class "Default")
      (node (ref "U1") (pin "M15") (pinfunction "PH12_M15") (pintype "passive+no_connect"))
    )
    (net (code "160") (name "unconnected-(U1H-PH15-PadD13)") (class "Default")
      (node (ref "U1") (pin "D13") (pinfunction "PH15_D13") (pintype "passive+no_connect"))
    )
    (net (code "161") (name "unconnected-(U1I-PI12-PadE3)") (class "Default")
      (node (ref "U1") (pin "E3") (pinfunction "PI12_E3") (pintype "passive+no_connect"))
    )
    (net (code "162") (name "unconnected-(U1I-PI13-PadG3)") (class "Default")
      (node (ref "U1") (pin "G3") (pinfunction "PI13_G3") (pintype "passive+no_connect"))
    )
    (net (code "163") (name "unconnected-(U1I-PI14-PadH3)") (class "Default")
      (node (ref "U1") (pin "H3") (pinfunction "PI14_H3") (pintype "passive+no_connect"))
    )
    (net (code "164") (name "unconnected-(U1I-PI15-PadG4)") (class "Default")
      (node (ref "U1") (pin "G4") (pinfunction "PI15_G4") (pintype "passive+no_connect"))
    )
    (net (code "165") (name "unconnected-(U1J-PJ0-PadR6)") (class "Default")
      (node (ref "U1") (pin "R6") (pinfunction "PJ0_R6") (pintype "passive+no_connect"))
    )
    (net (code "166") (name "unconnected-(U1J-PJ1-PadR7)") (class "Default")
      (node (ref "U1") (pin "R7") (pinfunction "PJ1_R7") (pintype "passive+no_connect"))
    )
    (net (code "167") (name "unconnected-(U1J-PJ2-PadP7)") (class "Default")
      (node (ref "U1") (pin "P7") (pinfunction "PJ2_P7") (pintype "passive+no_connect"))
    )
    (net (code "168") (name "unconnected-(U1J-PJ3-PadN8)") (class "Default")
      (node (ref "U1") (pin "N8") (pinfunction "PJ3_N8") (pintype "passive+no_connect"))
    )
    (net (code "169") (name "unconnected-(U1J-PJ4-PadM9)") (class "Default")
      (node (ref "U1") (pin "M9") (pinfunction "PJ4_M9") (pintype "passive+no_connect"))
    )
    (net (code "170") (name "unconnected-(U1J-PJ5-PadM14)") (class "Default")
      (node (ref "U1") (pin "M14") (pinfunction "PJ5_M14") (pintype "passive+no_connect"))
    )
    (net (code "171") (name "unconnected-(U1J-PJ6-PadK12)") (class "Default")
      (node (ref "U1") (pin "K12") (pinfunction "PJ6_K12") (pintype "passive+no_connect"))
    )
    (net (code "172") (name "unconnected-(U1J-PJ7-PadJ12)") (class "Default")
      (node (ref "U1") (pin "J12") (pinfunction "PJ7_J12") (pintype "passive+no_connect"))
    )
    (net (code "173") (name "unconnected-(U1J-PJ8-PadH12)") (class "Default")
      (node (ref "U1") (pin "H12") (pinfunction "PJ8_H12") (pintype "passive+no_connect"))
    )
    (net (code "174") (name "unconnected-(U1J-PJ9-PadJ13)") (class "Default")
      (node (ref "U1") (pin "J13") (pinfunction "PJ9_J13") (pintype "passive+no_connect"))
    )
    (net (code "175") (name "unconnected-(U1J-PJ10-PadH13)") (class "Default")
      (node (ref "U1") (pin "H13") (pinfunction "PJ10_H13") (pintype "passive+no_connect"))
    )
    (net (code "176") (name "unconnected-(U1J-PJ11-PadG12)") (class "Default")
      (node (ref "U1") (pin "G12") (pinfunction "PJ11_G12") (pintype "passive+no_connect"))
    )
    (net (code "177") (name "unconnected-(U1J-PJ12-PadB10)") (class "Default")
      (node (ref "U1") (pin "B10") (pinfunction "PJ12_B10") (pintype "passive+no_connect"))
    )
    (net (code "178") (name "unconnected-(U1J-PJ13-PadB9)") (class "Default")
      (node (ref "U1") (pin "B9") (pinfunction "PJ13_B9") (pintype "passive+no_connect"))
    )
    (net (code "179") (name "unconnected-(U1J-PJ14-PadC9)") (class "Default")
      (node (ref "U1") (pin "C9") (pinfunction "PJ14_C9") (pintype "passive+no_connect"))
    )
    (net (code "180") (name "unconnected-(U1J-PJ15-PadD10)") (class "Default")
      (node (ref "U1") (pin "D10") (pinfunction "PJ15_D10") (pintype "passive+no_connect"))
    )
    (net (code "181") (name "unconnected-(U1K-PK0-PadG13)") (class "Default")
      (node (ref "U1") (pin "G13") (pinfunction "PK0_G13") (pintype "passive+no_connect"))
    )
    (net (code "182") (name "unconnected-(U1K-PK1-PadF12)") (class "Default")
      (node (ref "U1") (pin "F12") (pinfunction "PK1_F12") (pintype "passive+no_connect"))
    )
    (net (code "183") (name "unconnected-(U1K-PK2-PadF13)") (class "Default")
      (node (ref "U1") (pin "F13") (pinfunction "PK2_F13") (pintype "passive+no_connect"))
    )
    (net (code "184") (name "unconnected-(U1K-PK3-PadD8)") (class "Default")
      (node (ref "U1") (pin "D8") (pinfunction "PK3_D8") (pintype "passive+no_connect"))
    )
    (net (code "185") (name "unconnected-(U1K-PK4-PadD7)") (class "Default")
      (node (ref "U1") (pin "D7") (pinfunction "PK4_D7") (pintype "passive+no_connect"))
    )
    (net (code "186") (name "unconnected-(U1K-PK5-PadC6)") (class "Default")
      (node (ref "U1") (pin "C6") (pinfunction "PK5_C6") (pintype "passive+no_connect"))
    )
    (net (code "187") (name "unconnected-(U1K-PK6-PadC5)") (class "Default")
      (node (ref "U1") (pin "C5") (pinfunction "PK6_C5") (pintype "passive+no_connect"))
    )
    (net (code "188") (name "unconnected-(U1K-PK7-PadC4)") (class "Default")
      (node (ref "U1") (pin "C4") (pinfunction "PK7_C4") (pintype "passive+no_connect"))
    )
  )
)
